# ActiveMoCapDeck_80mm.net
KiCad netlist of a schematic drawn in EasyEDA Pro
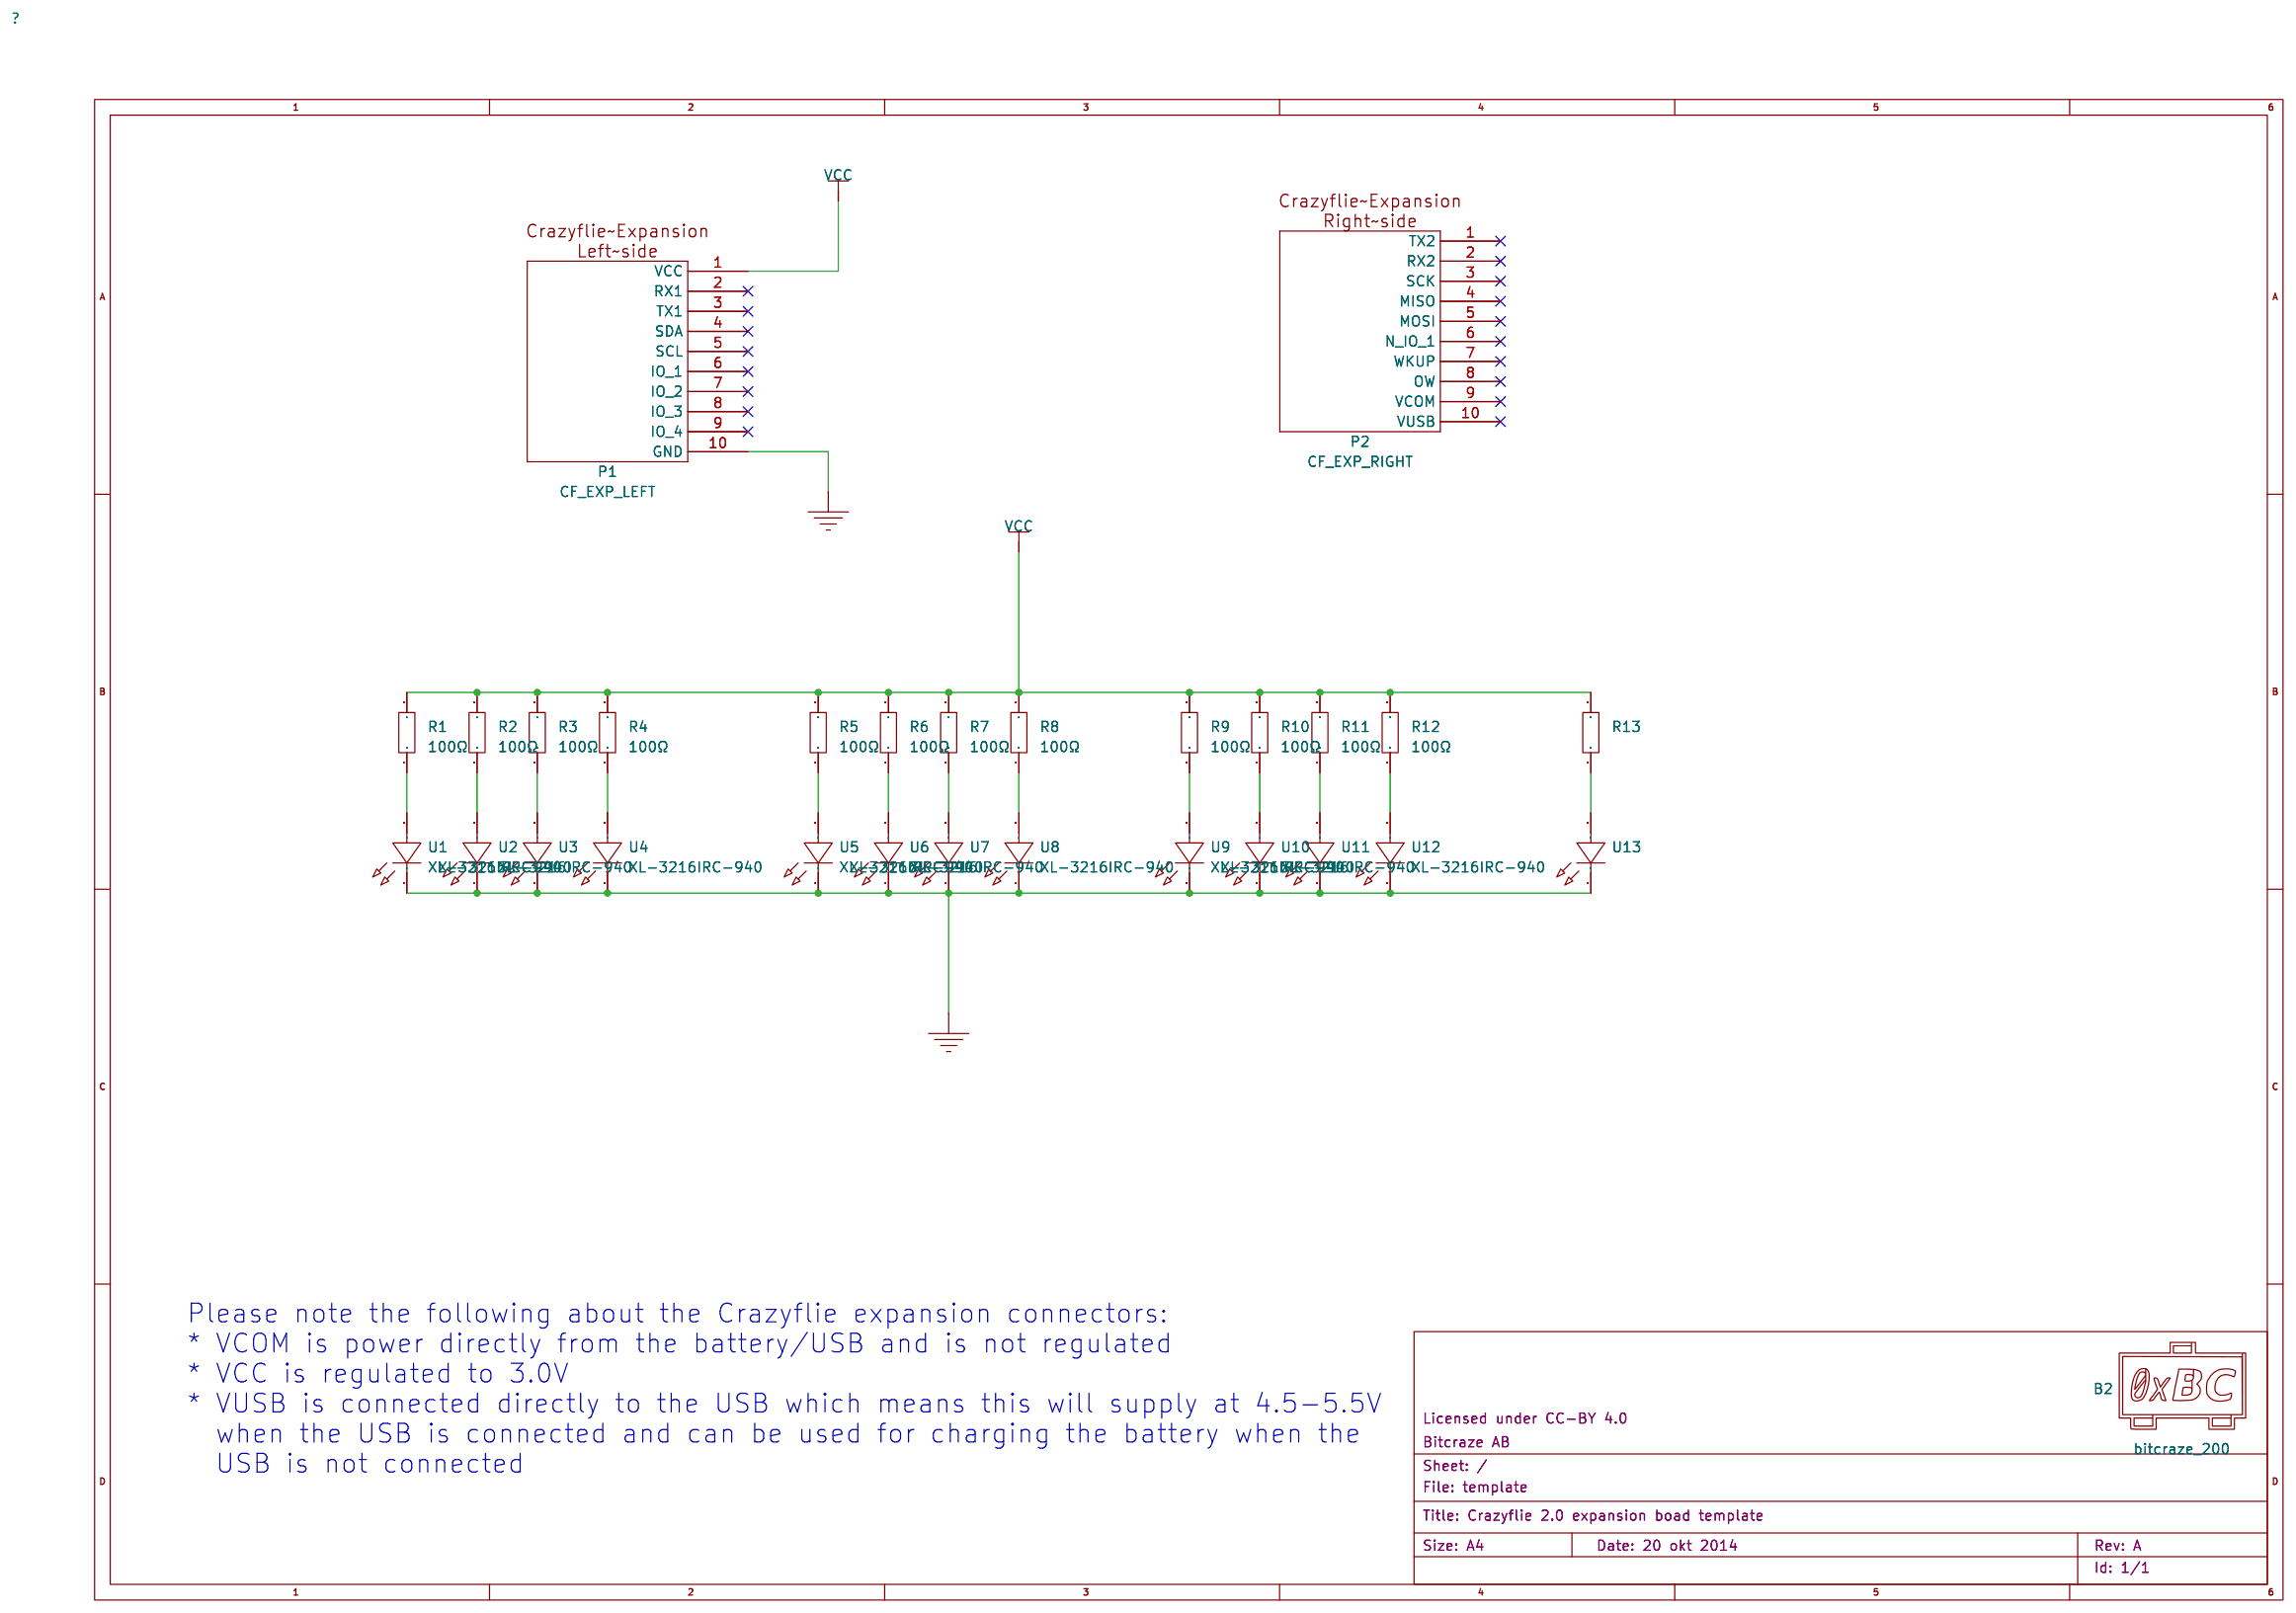
[diagram p0: schematic sheet]

(export (version "E")
  (design (tool "Eeschema 10.0.6"))
  (components
    (comp (ref "B2") (value "bitcraze_200") (libsource (lib "easyedapro") (part "bitcraze_200")))
    (comp (ref "P1") (value "CF_EXP_LEFT") (libsource (lib "easyedapro") (part "CF_EXP_LEFT")))
    (comp (ref "P2") (value "CF_EXP_RIGHT") (libsource (lib "easyedapro") (part "CF_EXP_RIGHT")))
    (comp (ref "R1")
      (value "100Ω")
      (footprint "easyedapro:R1206")
      (description "电阻类型:厚膜电阻;阻值:100Ω;精度:±1%;功率:250mW;最大工作电压:200V;温度系数:±100ppm/°C;")
      (fields
        (field (name "Manufacturer Part") "1206W4F1000T5E")
        (field (name "Manufacturer") "UNI-ROYAL(厚声)")
      )
      (libsource (lib "easyedapro") (part "1206W4F1000T5E"))
    )
    (comp (ref "R2")
      (value "100Ω")
      (footprint "easyedapro:R1206")
      (description "电阻类型:厚膜电阻;阻值:100Ω;精度:±1%;功率:250mW;最大工作电压:200V;温度系数:±100ppm/°C;")
      (fields
        (field (name "Manufacturer Part") "1206W4F1000T5E")
        (field (name "Manufacturer") "UNI-ROYAL(厚声)")
      )
      (libsource (lib "easyedapro") (part "1206W4F1000T5E"))
    )
    (comp (ref "R3")
      (value "100Ω")
      (footprint "easyedapro:R1206")
      (description "电阻类型:厚膜电阻;阻值:100Ω;精度:±1%;功率:250mW;最大工作电压:200V;温度系数:±100ppm/°C;")
      (fields
        (field (name "Manufacturer Part") "1206W4F1000T5E")
        (field (name "Manufacturer") "UNI-ROYAL(厚声)")
      )
      (libsource (lib "easyedapro") (part "1206W4F1000T5E"))
    )
    (comp (ref "R4")
      (value "100Ω")
      (footprint "easyedapro:R1206")
      (description "电阻类型:厚膜电阻;阻值:100Ω;精度:±1%;功率:250mW;最大工作电压:200V;温度系数:±100ppm/°C;")
      (fields
        (field (name "Manufacturer Part") "1206W4F1000T5E")
        (field (name "Manufacturer") "UNI-ROYAL(厚声)")
      )
      (libsource (lib "easyedapro") (part "1206W4F1000T5E"))
    )
    (comp (ref "R5")
      (value "100Ω")
      (footprint "easyedapro:R1206")
      (description "电阻类型:厚膜电阻;阻值:100Ω;精度:±1%;功率:250mW;最大工作电压:200V;温度系数:±100ppm/°C;")
      (fields
        (field (name "Manufacturer Part") "1206W4F1000T5E")
        (field (name "Manufacturer") "UNI-ROYAL(厚声)")
      )
      (libsource (lib "easyedapro") (part "1206W4F1000T5E"))
    )
    (comp (ref "R6")
      (value "100Ω")
      (footprint "easyedapro:R1206")
      (description "电阻类型:厚膜电阻;阻值:100Ω;精度:±1%;功率:250mW;最大工作电压:200V;温度系数:±100ppm/°C;")
      (fields
        (field (name "Manufacturer Part") "1206W4F1000T5E")
        (field (name "Manufacturer") "UNI-ROYAL(厚声)")
      )
      (libsource (lib "easyedapro") (part "1206W4F1000T5E"))
    )
    (comp (ref "R7")
      (value "100Ω")
      (footprint "easyedapro:R1206")
      (description "电阻类型:厚膜电阻;阻值:100Ω;精度:±1%;功率:250mW;最大工作电压:200V;温度系数:±100ppm/°C;")
      (fields
        (field (name "Manufacturer Part") "1206W4F1000T5E")
        (field (name "Manufacturer") "UNI-ROYAL(厚声)")
      )
      (libsource (lib "easyedapro") (part "1206W4F1000T5E"))
    )
    (comp (ref "R8")
      (value "100Ω")
      (footprint "easyedapro:R1206")
      (description "电阻类型:厚膜电阻;阻值:100Ω;精度:±1%;功率:250mW;最大工作电压:200V;温度系数:±100ppm/°C;")
      (fields
        (field (name "Manufacturer Part") "1206W4F1000T5E")
        (field (name "Manufacturer") "UNI-ROYAL(厚声)")
      )
      (libsource (lib "easyedapro") (part "1206W4F1000T5E"))
    )
    (comp (ref "R9")
      (value "100Ω")
      (footprint "easyedapro:R1206")
      (description "电阻类型:厚膜电阻;阻值:100Ω;精度:±1%;功率:250mW;最大工作电压:200V;温度系数:±100ppm/°C;")
      (fields
        (field (name "Manufacturer Part") "1206W4F1000T5E")
        (field (name "Manufacturer") "UNI-ROYAL(厚声)")
      )
      (libsource (lib "easyedapro") (part "1206W4F1000T5E"))
    )
    (comp (ref "R10")
      (value "100Ω")
      (footprint "easyedapro:R1206")
      (description "电阻类型:厚膜电阻;阻值:100Ω;精度:±1%;功率:250mW;最大工作电压:200V;温度系数:±100ppm/°C;")
      (fields
        (field (name "Manufacturer Part") "1206W4F1000T5E")
        (field (name "Manufacturer") "UNI-ROYAL(厚声)")
      )
      (libsource (lib "easyedapro") (part "1206W4F1000T5E"))
    )
    (comp (ref "R11")
      (value "100Ω")
      (footprint "easyedapro:R1206")
      (description "电阻类型:厚膜电阻;阻值:100Ω;精度:±1%;功率:250mW;最大工作电压:200V;温度系数:±100ppm/°C;")
      (fields
        (field (name "Manufacturer Part") "1206W4F1000T5E")
        (field (name "Manufacturer") "UNI-ROYAL(厚声)")
      )
      (libsource (lib "easyedapro") (part "1206W4F1000T5E"))
    )
    (comp (ref "R12")
      (value "100Ω")
      (footprint "easyedapro:R1206")
      (description "电阻类型:厚膜电阻;阻值:100Ω;精度:±1%;功率:250mW;最大工作电压:200V;温度系数:±100ppm/°C;")
      (fields
        (field (name "Manufacturer Part") "1206W4F1000T5E")
        (field (name "Manufacturer") "UNI-ROYAL(厚声)")
      )
      (libsource (lib "easyedapro") (part "1206W4F1000T5E"))
    )
    (comp (ref "R13")
      (value "100Ω")
      (footprint "easyedapro:R1206")
      (description "电阻类型:厚膜电阻;阻值:100Ω;精度:±1%;功率:250mW;最大工作电压:200V;温度系数:±100ppm/°C;")
      (fields
        (field (name "Manufacturer Part") "1206W4F1000T5E")
        (field (name "Manufacturer") "UNI-ROYAL(厚声)")
      )
      (libsource (lib "easyedapro") (part "1206W4F1000T5E"))
    )
    (comp (ref "U1")
      (value "XL-3216IRC-940")
      (footprint "easyedapro:LED1206-RD")
      (description "正向电压:1.2V~1.6V;耗散功率:70mW;波长:939nm~946nm;辐射强度:-;正向电流-DC (If):30mA;直流反向耐压:5V;视角:120°;")
      (fields (field (name "Manufacturer") "XINGLIGHT(成兴光)"))
      (libsource (lib "easyedapro") (part "XL-3216IRC-940"))
    )
    (comp (ref "U2")
      (value "XL-3216IRC-940")
      (footprint "easyedapro:LED1206-RD")
      (description "正向电压:1.2V~1.6V;耗散功率:70mW;波长:939nm~946nm;辐射强度:-;正向电流-DC (If):30mA;直流反向耐压:5V;视角:120°;")
      (fields (field (name "Manufacturer") "XINGLIGHT(成兴光)"))
      (libsource (lib "easyedapro") (part "XL-3216IRC-940"))
    )
    (comp (ref "U3")
      (value "XL-3216IRC-940")
      (footprint "easyedapro:LED1206-RD")
      (description "正向电压:1.2V~1.6V;耗散功率:70mW;波长:939nm~946nm;辐射强度:-;正向电流-DC (If):30mA;直流反向耐压:5V;视角:120°;")
      (fields (field (name "Manufacturer") "XINGLIGHT(成兴光)"))
      (libsource (lib "easyedapro") (part "XL-3216IRC-940"))
    )
    (comp (ref "U4")
      (value "XL-3216IRC-940")
      (footprint "easyedapro:LED1206-RD")
      (description "正向电压:1.2V~1.6V;耗散功率:70mW;波长:939nm~946nm;辐射强度:-;正向电流-DC (If):30mA;直流反向耐压:5V;视角:120°;")
      (fields (field (name "Manufacturer") "XINGLIGHT(成兴光)"))
      (libsource (lib "easyedapro") (part "XL-3216IRC-940"))
    )
    (comp (ref "U5")
      (value "XL-3216IRC-940")
      (footprint "easyedapro:LED1206-RD")
      (description "正向电压:1.2V~1.6V;耗散功率:70mW;波长:939nm~946nm;辐射强度:-;正向电流-DC (If):30mA;直流反向耐压:5V;视角:120°;")
      (fields (field (name "Manufacturer") "XINGLIGHT(成兴光)"))
      (libsource (lib "easyedapro") (part "XL-3216IRC-940"))
    )
    (comp (ref "U6")
      (value "XL-3216IRC-940")
      (footprint "easyedapro:LED1206-RD")
      (description "正向电压:1.2V~1.6V;耗散功率:70mW;波长:939nm~946nm;辐射强度:-;正向电流-DC (If):30mA;直流反向耐压:5V;视角:120°;")
      (fields (field (name "Manufacturer") "XINGLIGHT(成兴光)"))
      (libsource (lib "easyedapro") (part "XL-3216IRC-940"))
    )
    (comp (ref "U7")
      (value "XL-3216IRC-940")
      (footprint "easyedapro:LED1206-RD")
      (description "正向电压:1.2V~1.6V;耗散功率:70mW;波长:939nm~946nm;辐射强度:-;正向电流-DC (If):30mA;直流反向耐压:5V;视角:120°;")
      (fields (field (name "Manufacturer") "XINGLIGHT(成兴光)"))
      (libsource (lib "easyedapro") (part "XL-3216IRC-940"))
    )
    (comp (ref "U8")
      (value "XL-3216IRC-940")
      (footprint "easyedapro:LED1206-RD")
      (description "正向电压:1.2V~1.6V;耗散功率:70mW;波长:939nm~946nm;辐射强度:-;正向电流-DC (If):30mA;直流反向耐压:5V;视角:120°;")
      (fields (field (name "Manufacturer") "XINGLIGHT(成兴光)"))
      (libsource (lib "easyedapro") (part "XL-3216IRC-940"))
    )
    (comp (ref "U9")
      (value "XL-3216IRC-940")
      (footprint "easyedapro:LED1206-RD")
      (description "正向电压:1.2V~1.6V;耗散功率:70mW;波长:939nm~946nm;辐射强度:-;正向电流-DC (If):30mA;直流反向耐压:5V;视角:120°;")
      (fields (field (name "Manufacturer") "XINGLIGHT(成兴光)"))
      (libsource (lib "easyedapro") (part "XL-3216IRC-940"))
    )
    (comp (ref "U10")
      (value "XL-3216IRC-940")
      (footprint "easyedapro:LED1206-RD")
      (description "正向电压:1.2V~1.6V;耗散功率:70mW;波长:939nm~946nm;辐射强度:-;正向电流-DC (If):30mA;直流反向耐压:5V;视角:120°;")
      (fields (field (name "Manufacturer") "XINGLIGHT(成兴光)"))
      (libsource (lib "easyedapro") (part "XL-3216IRC-940"))
    )
    (comp (ref "U11")
      (value "XL-3216IRC-940")
      (footprint "easyedapro:LED1206-RD")
      (description "正向电压:1.2V~1.6V;耗散功率:70mW;波长:939nm~946nm;辐射强度:-;正向电流-DC (If):30mA;直流反向耐压:5V;视角:120°;")
      (fields (field (name "Manufacturer") "XINGLIGHT(成兴光)"))
      (libsource (lib "easyedapro") (part "XL-3216IRC-940"))
    )
    (comp (ref "U12")
      (value "XL-3216IRC-940")
      (footprint "easyedapro:LED1206-RD")
      (description "正向电压:1.2V~1.6V;耗散功率:70mW;波长:939nm~946nm;辐射强度:-;正向电流-DC (If):30mA;直流反向耐压:5V;视角:120°;")
      (fields (field (name "Manufacturer") "XINGLIGHT(成兴光)"))
      (libsource (lib "easyedapro") (part "XL-3216IRC-940"))
    )
    (comp (ref "U13")
      (value "XL-3216IRC-940")
      (footprint "easyedapro:LED1206-RD")
      (description "正向电压:1.2V~1.6V;耗散功率:70mW;波长:939nm~946nm;辐射强度:-;正向电流-DC (If):30mA;直流反向耐压:5V;视角:120°;")
      (fields (field (name "Manufacturer") "XINGLIGHT(成兴光)"))
      (libsource (lib "easyedapro") (part "XL-3216IRC-940"))
    )
  )
  (nets
    (net (code "1") (name "GND") (class "Default")
      (node (ref "P1") (pin "10") (pinfunction "GND_10") (pintype "unspecified"))
      (node (ref "U1") (pin "1") (pinfunction "K_1") (pintype "unspecified"))
      (node (ref "U10") (pin "1") (pinfunction "K_1") (pintype "unspecified"))
      (node (ref "U11") (pin "1") (pinfunction "K_1") (pintype "unspecified"))
      (node (ref "U12") (pin "1") (pinfunction "K_1") (pintype "unspecified"))
      (node (ref "U13") (pin "1") (pinfunction "K_1") (pintype "unspecified"))
      (node (ref "U2") (pin "1") (pinfunction "K_1") (pintype "unspecified"))
      (node (ref "U3") (pin "1") (pinfunction "K_1") (pintype "unspecified"))
      (node (ref "U4") (pin "1") (pinfunction "K_1") (pintype "unspecified"))
      (node (ref "U5") (pin "1") (pinfunction "K_1") (pintype "unspecified"))
      (node (ref "U6") (pin "1") (pinfunction "K_1") (pintype "unspecified"))
      (node (ref "U7") (pin "1") (pinfunction "K_1") (pintype "unspecified"))
      (node (ref "U8") (pin "1") (pinfunction "K_1") (pintype "unspecified"))
      (node (ref "U9") (pin "1") (pinfunction "K_1") (pintype "unspecified"))
    )
    (net (code "2") (name "Net-(U1-A)") (class "Default")
      (node (ref "R1") (pin "1") (pinfunction "1_1") (pintype "input"))
      (node (ref "U1") (pin "2") (pinfunction "A_2") (pintype "unspecified"))
    )
    (net (code "3") (name "Net-(U2-A)") (class "Default")
      (node (ref "R2") (pin "1") (pinfunction "1_1") (pintype "input"))
      (node (ref "U2") (pin "2") (pinfunction "A_2") (pintype "unspecified"))
    )
    (net (code "4") (name "Net-(U3-A)") (class "Default")
      (node (ref "R3") (pin "1") (pinfunction "1_1") (pintype "input"))
      (node (ref "U3") (pin "2") (pinfunction "A_2") (pintype "unspecified"))
    )
    (net (code "5") (name "Net-(U4-A)") (class "Default")
      (node (ref "R4") (pin "1") (pinfunction "1_1") (pintype "input"))
      (node (ref "U4") (pin "2") (pinfunction "A_2") (pintype "unspecified"))
    )
    (net (code "6") (name "Net-(U5-A)") (class "Default")
      (node (ref "R5") (pin "1") (pinfunction "1_1") (pintype "input"))
      (node (ref "U5") (pin "2") (pinfunction "A_2") (pintype "unspecified"))
    )
    (net (code "7") (name "Net-(U6-A)") (class "Default")
      (node (ref "R6") (pin "1") (pinfunction "1_1") (pintype "input"))
      (node (ref "U6") (pin "2") (pinfunction "A_2") (pintype "unspecified"))
    )
    (net (code "8") (name "Net-(U7-A)") (class "Default")
      (node (ref "R7") (pin "1") (pinfunction "1_1") (pintype "input"))
      (node (ref "U7") (pin "2") (pinfunction "A_2") (pintype "unspecified"))
    )
    (net (code "9") (name "Net-(U8-A)") (class "Default")
      (node (ref "R8") (pin "1") (pinfunction "1_1") (pintype "input"))
      (node (ref "U8") (pin "2") (pinfunction "A_2") (pintype "unspecified"))
    )
    (net (code "10") (name "Net-(U9-A)") (class "Default")
      (node (ref "R9") (pin "1") (pinfunction "1_1") (pintype "input"))
      (node (ref "U9") (pin "2") (pinfunction "A_2") (pintype "unspecified"))
    )
    (net (code "11") (name "Net-(U10-A)") (class "Default")
      (node (ref "R10") (pin "1") (pinfunction "1_1") (pintype "input"))
      (node (ref "U10") (pin "2") (pinfunction "A_2") (pintype "unspecified"))
    )
    (net (code "12") (name "Net-(U11-A)") (class "Default")
      (node (ref "R11") (pin "1") (pinfunction "1_1") (pintype "input"))
      (node (ref "U11") (pin "2") (pinfunction "A_2") (pintype "unspecified"))
    )
    (net (code "13") (name "Net-(U12-A)") (class "Default")
      (node (ref "R12") (pin "1") (pinfunction "1_1") (pintype "input"))
      (node (ref "U12") (pin "2") (pinfunction "A_2") (pintype "unspecified"))
    )
    (net (code "14") (name "Net-(U13-A)") (class "Default")
      (node (ref "R13") (pin "1") (pinfunction "1_1") (pintype "input"))
      (node (ref "U13") (pin "2") (pinfunction "A_2") (pintype "unspecified"))
    )
    (net (code "15") (name "VCC") (class "Default")
      (node (ref "P1") (pin "1") (pinfunction "VCC_1") (pintype "unspecified"))
      (node (ref "R1") (pin "2") (pinfunction "2_2") (pintype "input"))
      (node (ref "R10") (pin "2") (pinfunction "2_2") (pintype "input"))
      (node (ref "R11") (pin "2") (pinfunction "2_2") (pintype "input"))
      (node (ref "R12") (pin "2") (pinfunction "2_2") (pintype "input"))
      (node (ref "R13") (pin "2") (pinfunction "2_2") (pintype "input"))
      (node (ref "R2") (pin "2") (pinfunction "2_2") (pintype "input"))
      (node (ref "R3") (pin "2") (pinfunction "2_2") (pintype "input"))
      (node (ref "R4") (pin "2") (pinfunction "2_2") (pintype "input"))
      (node (ref "R5") (pin "2") (pinfunction "2_2") (pintype "input"))
      (node (ref "R6") (pin "2") (pinfunction "2_2") (pintype "input"))
      (node (ref "R7") (pin "2") (pinfunction "2_2") (pintype "input"))
      (node (ref "R8") (pin "2") (pinfunction "2_2") (pintype "input"))
      (node (ref "R9") (pin "2") (pinfunction "2_2") (pintype "input"))
    )
    (net (code "16") (name "unconnected-(P1-IO_1-Pad6)") (class "Default")
      (node (ref "P1") (pin "6") (pinfunction "IO_1_6") (pintype "unspecified+no_connect"))
    )
    (net (code "17") (name "unconnected-(P1-IO_2-Pad7)") (class "Default")
      (node (ref "P1") (pin "7") (pinfunction "IO_2_7") (pintype "unspecified+no_connect"))
    )
    (net (code "18") (name "unconnected-(P1-IO_3-Pad8)") (class "Default")
      (node (ref "P1") (pin "8") (pinfunction "IO_3_8") (pintype "unspecified+no_connect"))
    )
    (net (code "19") (name "unconnected-(P1-IO_4-Pad9)") (class "Default")
      (node (ref "P1") (pin "9") (pinfunction "IO_4_9") (pintype "unspecified+no_connect"))
    )
    (net (code "20") (name "unconnected-(P1-RX1-Pad2)") (class "Default")
      (node (ref "P1") (pin "2") (pinfunction "RX1_2") (pintype "unspecified+no_connect"))
    )
    (net (code "21") (name "unconnected-(P1-SCL-Pad5)") (class "Default")
      (node (ref "P1") (pin "5") (pinfunction "SCL_5") (pintype "unspecified+no_connect"))
    )
    (net (code "22") (name "unconnected-(P1-SDA-Pad4)") (class "Default")
      (node (ref "P1") (pin "4") (pinfunction "SDA_4") (pintype "unspecified+no_connect"))
    )
    (net (code "23") (name "unconnected-(P1-TX1-Pad3)") (class "Default")
      (node (ref "P1") (pin "3") (pinfunction "TX1_3") (pintype "unspecified+no_connect"))
    )
    (net (code "24") (name "unconnected-(P2-MISO-Pad4)") (class "Default")
      (node (ref "P2") (pin "4") (pinfunction "MISO_4") (pintype "unspecified+no_connect"))
    )
    (net (code "25") (name "unconnected-(P2-MOSI-Pad5)") (class "Default")
      (node (ref "P2") (pin "5") (pinfunction "MOSI_5") (pintype "unspecified+no_connect"))
    )
    (net (code "26") (name "unconnected-(P2-N_IO_1-Pad6)") (class "Default")
      (node (ref "P2") (pin "6") (pinfunction "N_IO_1_6") (pintype "unspecified+no_connect"))
    )
    (net (code "27") (name "unconnected-(P2-OW-Pad8)") (class "Default")
      (node (ref "P2") (pin "8") (pinfunction "OW_8") (pintype "unspecified+no_connect"))
    )
    (net (code "28") (name "unconnected-(P2-RX2-Pad2)") (class "Default")
      (node (ref "P2") (pin "2") (pinfunction "RX2_2") (pintype "unspecified+no_connect"))
    )
    (net (code "29") (name "unconnected-(P2-SCK-Pad3)") (class "Default")
      (node (ref "P2") (pin "3") (pinfunction "SCK_3") (pintype "unspecified+no_connect"))
    )
    (net (code "30") (name "unconnected-(P2-TX2-Pad1)") (class "Default")
      (node (ref "P2") (pin "1") (pinfunction "TX2_1") (pintype "unspecified+no_connect"))
    )
    (net (code "31") (name "unconnected-(P2-VCOM-Pad9)") (class "Default")
      (node (ref "P2") (pin "9") (pinfunction "VCOM_9") (pintype "unspecified+no_connect"))
    )
    (net (code "32") (name "unconnected-(P2-VUSB-Pad10)") (class "Default")
      (node (ref "P2") (pin "10") (pinfunction "VUSB_10") (pintype "unspecified+no_connect"))
    )
    (net (code "33") (name "unconnected-(P2-WKUP-Pad7)") (class "Default")
      (node (ref "P2") (pin "7") (pinfunction "WKUP_7") (pintype "unspecified+no_connect"))
    )
  )
)
